# misc.net
KiCad netlist of a schematic drawn in Altium Designer
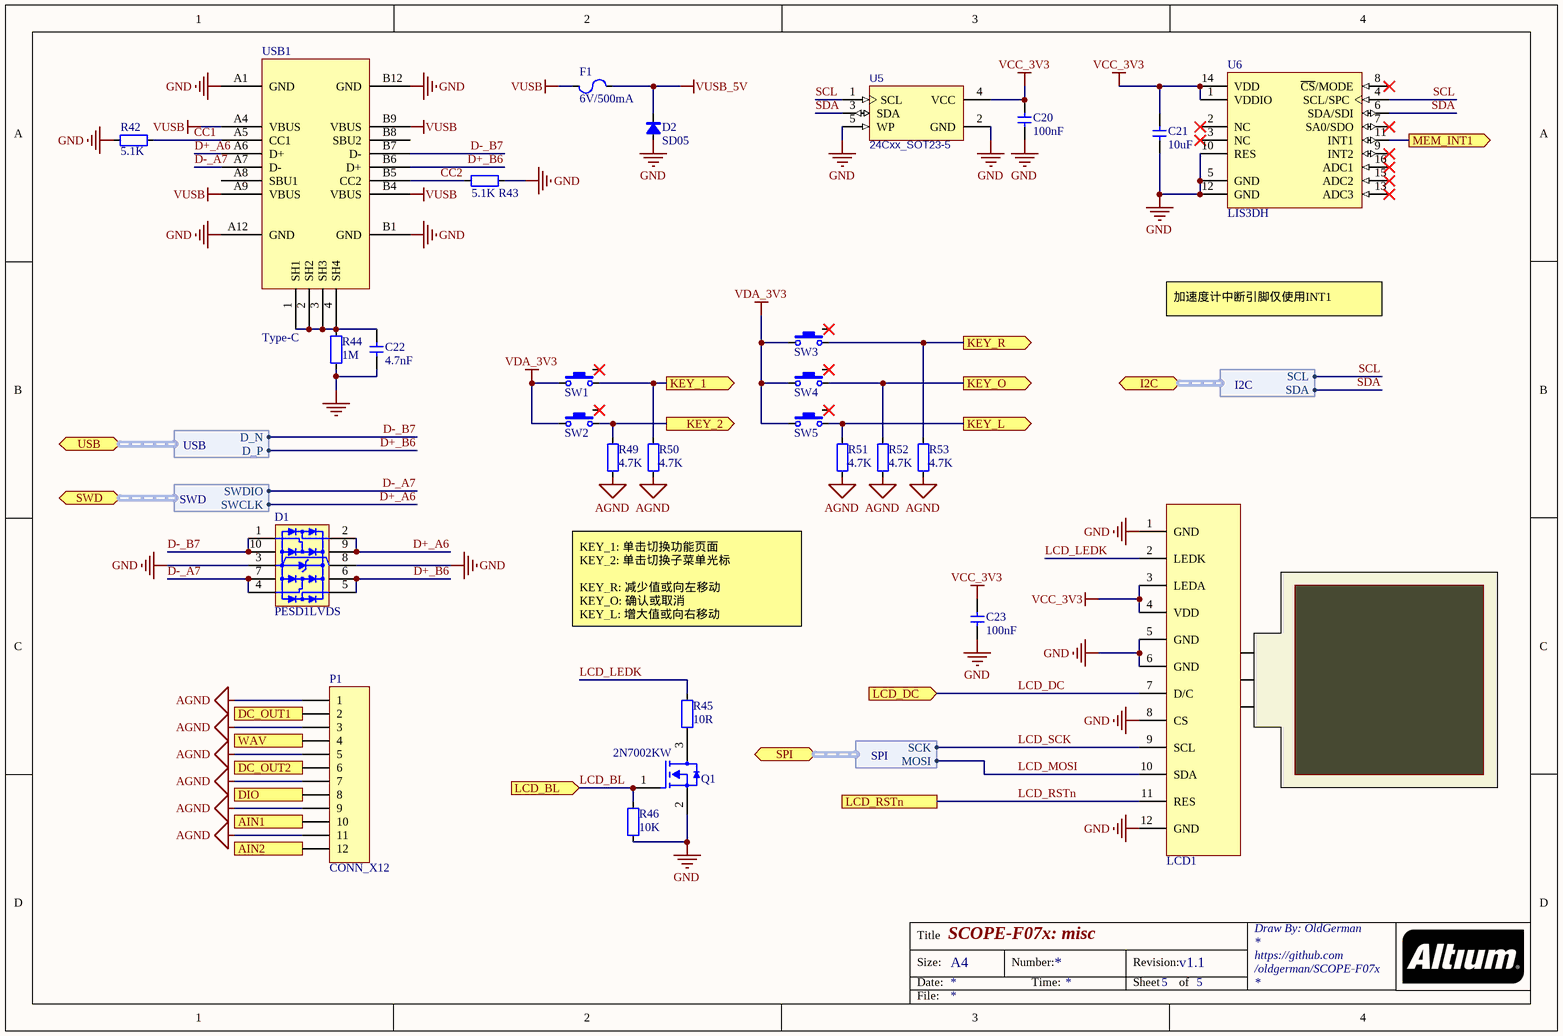
[diagram p0: misc.SchDoc]

(export (version "E")
  (design (tool "Eeschema 10.0.6"))
  (components
    (comp (ref "C20")
      (value "100nF")
      (footprint "C0402")
      (description "Capacitor")
      (libsource (lib "ODG_AD_Lib") (part "CAP"))
    )
    (comp (ref "C21")
      (value "10uF")
      (footprint "C0402")
      (description "Capacitor")
      (libsource (lib "ODG_AD_Lib") (part "CAP"))
    )
    (comp (ref "C22")
      (value "4.7nF")
      (footprint "C0402")
      (description "Capacitor")
      (libsource (lib "") (part "CAP_1"))
    )
    (comp (ref "C23")
      (value "100nF")
      (footprint "C0402")
      (description "Capacitor")
      (libsource (lib "") (part "CAP_1"))
    )
    (comp (ref "D1")
      (value "PESD1LVDS")
      (footprint "DFN2510-10_SOT1165-1")
      (description "Ultra-Low Capacitance TVS Protection")
      (fields (field (name "版权归属") "源创客"))
      (libsource (lib "ODG_AD_Lib") (part "PESD1LVDS"))
    )
    (comp (ref "D2")
      (value "SD05")
      (footprint "SOD-323")
      (description "单向 5V TVS")
      (libsource (lib "ODG_AD_Lib") (part "DIODE"))
    )
    (comp (ref "F1")
      (value "6V/500mA")
      (footprint "FUSE0603_0.5MM")
      (description "贴片自恢复保险丝")
      (libsource (lib "ODG_AD_Lib") (part "FUSE"))
    )
    (comp (ref "LCD1")
      (value "LCD_240x240")
      (footprint "LCD-240X240-1.54INCH_FLUSH_FRONT")
      (libsource (lib "ODG_AD_Lib") (part "LCD_240x240"))
    )
    (comp (ref "P1")
      (value "CONN_X12")
      (footprint "2.54MM_FEMALE_1x12_180H")
      (libsource (lib "ODG_Project") (part "CONN_X12"))
    )
    (comp (ref "Q1")
      (value "2N7002KW")
      (footprint "DIODES SOT-323-3")
      (description "N-MOS")
      (libsource (lib "ODG_AD_Lib") (part "N-MOS_123"))
    )
    (comp (ref "R42")
      (value "5.1K")
      (footprint "R0402")
      (description "Resistor")
      (libsource (lib "") (part "RES_3"))
    )
    (comp (ref "R43")
      (value "5.1K")
      (footprint "R0402")
      (description "Resistor")
      (libsource (lib "") (part "RES_1"))
    )
    (comp (ref "R44")
      (value "1M")
      (footprint "R0402")
      (description "Resistor")
      (libsource (lib "ODG_AD_Lib") (part "RES"))
    )
    (comp (ref "R45")
      (value "10R")
      (footprint "R0603")
      (description "Resistor")
      (libsource (lib "") (part "RES_2"))
    )
    (comp (ref "R46")
      (value "10K")
      (footprint "R0402")
      (description "Resistor")
      (libsource (lib "") (part "RES_2"))
    )
    (comp (ref "R49")
      (value "4.7K")
      (footprint "R0402")
      (description "Resistor")
      (libsource (lib "ODG_AD_Lib") (part "RES"))
    )
    (comp (ref "R50")
      (value "4.7K")
      (footprint "R0402")
      (description "Resistor")
      (libsource (lib "ODG_AD_Lib") (part "RES"))
    )
    (comp (ref "R51")
      (value "4.7K")
      (footprint "R0402")
      (description "Resistor")
      (libsource (lib "ODG_AD_Lib") (part "RES"))
    )
    (comp (ref "R52")
      (value "4.7K")
      (footprint "R0402")
      (description "Resistor")
      (libsource (lib "ODG_AD_Lib") (part "RES"))
    )
    (comp (ref "R53")
      (value "4.7K")
      (footprint "R0402")
      (description "Resistor")
      (libsource (lib "ODG_AD_Lib") (part "RES"))
    )
    (comp (ref "SW1")
      (value "Button-2P+PAD")
      (footprint "TACTILE_SWITCH_SMD_4.6x1.82x3.5mm_1TS003B")
      (description "Button")
      (libsource (lib "ODG_AD_Lib") (part "Button-2P+PAD"))
    )
    (comp (ref "SW2")
      (value "Button-2P+PAD")
      (footprint "TACTILE_SWITCH_SMD_4.6x1.82x3.5mm_1TS003B")
      (description "Button")
      (libsource (lib "ODG_AD_Lib") (part "Button-2P+PAD"))
    )
    (comp (ref "SW3")
      (value "Button-2P+PAD")
      (footprint "TACTILE_SWITCH_SMD_4.6x1.82x3.5mm_1TS003B")
      (description "Button")
      (libsource (lib "ODG_AD_Lib") (part "Button-2P+PAD"))
    )
    (comp (ref "SW4")
      (value "Button-2P+PAD")
      (footprint "TACTILE_SWITCH_SMD_4.6x1.82x3.5mm_1TS003B")
      (description "Button")
      (libsource (lib "ODG_AD_Lib") (part "Button-2P+PAD"))
    )
    (comp (ref "SW5")
      (value "Button-2P+PAD")
      (footprint "TACTILE_SWITCH_SMD_4.6x1.82x3.5mm_1TS003B")
      (description "Button")
      (libsource (lib "ODG_AD_Lib") (part "Button-2P+PAD"))
    )
    (comp (ref "U5")
      (value "24Cxx_SOT23-5")
      (footprint "MICROCHIP SOT-23-5 OT")
      (libsource (lib "ODG_AD_Lib") (part "24Cxx_SOT23-5"))
    )
    (comp (ref "U6") (value "LIS3DH") (footprint "LGA-16-3X3") (libsource (lib "ODG_AD_Lib") (part "LIS3DH")))
    (comp (ref "USB1")
      (value "Type-C")
      (footprint "Type-C-TOP")
      (libsource (lib "ODG_AD_Lib") (part "USB-Type-C_16P"))
    )
  )
  (nets
    (net (code "5") (name "/AIN1") (class "Default")
      (node (ref "P1") (pin "10") (pinfunction "10_10") (pintype "passive"))
    )
    (net (code "6") (name "/AIN2") (class "Default")
      (node (ref "P1") (pin "12") (pinfunction "12_12") (pintype "passive"))
    )
    (net (code "7") (name "/CC1") (class "Default")
      (node (ref "R42") (pin "1") (pinfunction "1_1") (pintype "passive"))
      (node (ref "USB1") (pin "A5") (pinfunction "CC1_A5") (pintype "passive"))
    )
    (net (code "8") (name "/CC2") (class "Default")
      (node (ref "R43") (pin "2") (pinfunction "2_2") (pintype "passive"))
      (node (ref "USB1") (pin "B5") (pinfunction "CC2_B5") (pintype "passive"))
    )
    (net (code "9") (name "/D+_A6") (class "Default")
      (node (ref "D1") (pin "2") (pinfunction "I/O_2") (pintype "passive"))
      (node (ref "D1") (pin "9") (pinfunction "GND_9") (pintype "passive"))
      (node (ref "USB1") (pin "A6") (pinfunction "D+_A6") (pintype "passive"))
    )
    (net (code "10") (name "/D+_B6") (class "Default")
      (node (ref "D1") (pin "5") (pinfunction "I/O_5") (pintype "passive"))
      (node (ref "D1") (pin "6") (pinfunction "GND_6") (pintype "passive"))
      (node (ref "USB1") (pin "B6") (pinfunction "D+_B6") (pintype "passive"))
    )
    (net (code "11") (name "/D-_A7") (class "Default")
      (node (ref "D1") (pin "4") (pinfunction "I/O_4") (pintype "passive"))
      (node (ref "D1") (pin "7") (pinfunction "GND_7") (pintype "passive"))
      (node (ref "USB1") (pin "A7") (pinfunction "D-_A7") (pintype "passive"))
    )
    (net (code "12") (name "/D-_B7") (class "Default")
      (node (ref "D1") (pin "1") (pinfunction "I/O_1") (pintype "passive"))
      (node (ref "D1") (pin "10") (pinfunction "GND_10") (pintype "passive"))
      (node (ref "USB1") (pin "B7") (pinfunction "D-_B7") (pintype "passive"))
    )
    (net (code "13") (name "/DC_OUT1") (class "Default")
      (node (ref "P1") (pin "2") (pinfunction "2_2") (pintype "passive"))
    )
    (net (code "14") (name "/DC_OUT2") (class "Default")
      (node (ref "P1") (pin "6") (pinfunction "6_6") (pintype "passive"))
    )
    (net (code "15") (name "/DIO") (class "Default")
      (node (ref "P1") (pin "8") (pinfunction "8_8") (pintype "passive"))
    )
    (net (code "16") (name "/KEY_1") (class "Default")
      (node (ref "R50") (pin "1") (pinfunction "1_1") (pintype "passive"))
      (node (ref "SW1") (pin "2") (pinfunction "2_2") (pintype "passive"))
    )
    (net (code "17") (name "/KEY_2") (class "Default")
      (node (ref "R49") (pin "1") (pinfunction "1_1") (pintype "passive"))
      (node (ref "SW2") (pin "2") (pinfunction "2_2") (pintype "passive"))
    )
    (net (code "18") (name "/KEY_L") (class "Default")
      (node (ref "R51") (pin "1") (pinfunction "1_1") (pintype "passive"))
      (node (ref "SW5") (pin "2") (pinfunction "2_2") (pintype "passive"))
    )
    (net (code "19") (name "/KEY_O") (class "Default")
      (node (ref "R52") (pin "1") (pinfunction "1_1") (pintype "passive"))
      (node (ref "SW4") (pin "2") (pinfunction "2_2") (pintype "passive"))
    )
    (net (code "20") (name "/KEY_R") (class "Default")
      (node (ref "R53") (pin "1") (pinfunction "1_1") (pintype "passive"))
      (node (ref "SW3") (pin "2") (pinfunction "2_2") (pintype "passive"))
    )
    (net (code "21") (name "/LCD_BL") (class "Default")
      (node (ref "Q1") (pin "1") (pinfunction "G_1") (pintype "passive"))
      (node (ref "R46") (pin "2") (pinfunction "2_2") (pintype "passive"))
    )
    (net (code "22") (name "/LCD_DC") (class "Default")
      (node (ref "LCD1") (pin "7") (pinfunction "D/C_7") (pintype "passive"))
    )
    (net (code "23") (name "/LCD_LEDK") (class "Default")
      (node (ref "LCD1") (pin "2") (pinfunction "LEDK_2") (pintype "passive"))
      (node (ref "R45") (pin "2") (pinfunction "2_2") (pintype "passive"))
    )
    (net (code "24") (name "/LCD_MOSI") (class "Default")
      (node (ref "LCD1") (pin "10") (pinfunction "SDA_10") (pintype "passive"))
    )
    (net (code "25") (name "/LCD_RSTn") (class "Default")
      (node (ref "LCD1") (pin "11") (pinfunction "RES_11") (pintype "passive"))
    )
    (net (code "26") (name "/LCD_SCK") (class "Default")
      (node (ref "LCD1") (pin "9") (pinfunction "SCL_9") (pintype "passive"))
    )
    (net (code "27") (name "/MEM_INT1") (class "Default")
      (node (ref "U6") (pin "11") (pinfunction "INT1_11") (pintype "bidirectional"))
    )
    (net (code "28") (name "/SCL") (class "Default")
      (node (ref "U5") (pin "1") (pinfunction "SCL_1") (pintype "input"))
      (node (ref "U6") (pin "4") (pinfunction "SCL/SPC_4") (pintype "input"))
    )
    (net (code "29") (name "/SDA") (class "Default")
      (node (ref "U5") (pin "3") (pinfunction "SDA_3") (pintype "bidirectional"))
      (node (ref "U6") (pin "6") (pinfunction "SDA/SDI_6") (pintype "bidirectional"))
    )
    (net (code "30") (name "/WAV") (class "Default")
      (node (ref "P1") (pin "4") (pinfunction "4_4") (pintype "passive"))
    )
    (net (code "35") (name "AGND") (class "Default")
      (node (ref "P1") (pin "1") (pinfunction "1_1") (pintype "passive"))
      (node (ref "P1") (pin "11") (pinfunction "11_11") (pintype "passive"))
      (node (ref "P1") (pin "3") (pinfunction "3_3") (pintype "passive"))
      (node (ref "P1") (pin "5") (pinfunction "5_5") (pintype "passive"))
      (node (ref "P1") (pin "7") (pinfunction "7_7") (pintype "passive"))
      (node (ref "P1") (pin "9") (pinfunction "9_9") (pintype "passive"))
      (node (ref "R49") (pin "2") (pinfunction "2_2") (pintype "passive"))
      (node (ref "R50") (pin "2") (pinfunction "2_2") (pintype "passive"))
      (node (ref "R51") (pin "2") (pinfunction "2_2") (pintype "passive"))
      (node (ref "R52") (pin "2") (pinfunction "2_2") (pintype "passive"))
      (node (ref "R53") (pin "2") (pinfunction "2_2") (pintype "passive"))
    )
    (net (code "36") (name "GND") (class "Default")
      (node (ref "C20") (pin "2") (pinfunction "2_2") (pintype "passive"))
      (node (ref "C21") (pin "2") (pinfunction "2_2") (pintype "passive"))
      (node (ref "C22") (pin "2") (pinfunction "2_2") (pintype "passive"))
      (node (ref "C23") (pin "1") (pinfunction "1_1") (pintype "passive"))
      (node (ref "D1") (pin "3") (pinfunction "GND_3") (pintype "passive"))
      (node (ref "D1") (pin "8") (pinfunction "GND_8") (pintype "passive"))
      (node (ref "D2") (pin "1") (pinfunction "A_1") (pintype "passive"))
      (node (ref "LCD1") (pin "1") (pinfunction "GND_1") (pintype "passive"))
      (node (ref "LCD1") (pin "12") (pinfunction "GND_12") (pintype "passive"))
      (node (ref "LCD1") (pin "5") (pinfunction "GND_5") (pintype "passive"))
      (node (ref "LCD1") (pin "6") (pinfunction "GND_6") (pintype "passive"))
      (node (ref "LCD1") (pin "8") (pinfunction "CS_8") (pintype "passive"))
      (node (ref "Q1") (pin "2") (pinfunction "S_2") (pintype "passive"))
      (node (ref "R42") (pin "2") (pinfunction "2_2") (pintype "passive"))
      (node (ref "R43") (pin "1") (pinfunction "1_1") (pintype "passive"))
      (node (ref "R44") (pin "2") (pinfunction "2_2") (pintype "passive"))
      (node (ref "R46") (pin "1") (pinfunction "1_1") (pintype "passive"))
      (node (ref "U5") (pin "2") (pinfunction "GND_2") (pintype "passive"))
      (node (ref "U5") (pin "5") (pinfunction "WP_5") (pintype "input"))
      (node (ref "U6") (pin "10") (pinfunction "RES_10") (pintype "power_in"))
      (node (ref "U6") (pin "12") (pinfunction "GND_12") (pintype "power_in"))
      (node (ref "U6") (pin "5") (pinfunction "GND_5") (pintype "power_in"))
      (node (ref "USB1") (pin "A1") (pinfunction "GND_A1") (pintype "passive"))
      (node (ref "USB1") (pin "A12") (pinfunction "GND_A12") (pintype "passive"))
      (node (ref "USB1") (pin "B1") (pinfunction "GND_B1") (pintype "passive"))
      (node (ref "USB1") (pin "B12") (pinfunction "GND_B12") (pintype "passive"))
    )
    (net (code "37") (name "Net-(Q1-D)") (class "Default")
      (node (ref "Q1") (pin "3") (pinfunction "D_3") (pintype "passive"))
      (node (ref "R45") (pin "1") (pinfunction "1_1") (pintype "passive"))
    )
    (net (code "38") (name "Net-(USB1-SH1)") (class "Default")
      (node (ref "C22") (pin "1") (pinfunction "1_1") (pintype "passive"))
      (node (ref "R44") (pin "1") (pinfunction "1_1") (pintype "passive"))
      (node (ref "USB1") (pin "1") (pinfunction "SH1_1") (pintype "passive"))
      (node (ref "USB1") (pin "2") (pinfunction "SH2_2") (pintype "passive"))
      (node (ref "USB1") (pin "3") (pinfunction "SH3_3") (pintype "passive"))
      (node (ref "USB1") (pin "4") (pinfunction "SH4_4") (pintype "passive"))
    )
    (net (code "39") (name "VCC_3V3") (class "Default")
      (node (ref "C20") (pin "1") (pinfunction "1_1") (pintype "passive"))
      (node (ref "C21") (pin "1") (pinfunction "1_1") (pintype "passive"))
      (node (ref "C23") (pin "2") (pinfunction "2_2") (pintype "passive"))
      (node (ref "LCD1") (pin "3") (pinfunction "LEDA_3") (pintype "passive"))
      (node (ref "LCD1") (pin "4") (pinfunction "VDD_4") (pintype "passive"))
      (node (ref "U5") (pin "4") (pinfunction "VCC_4") (pintype "passive"))
      (node (ref "U6") (pin "1") (pinfunction "VDDIO_1") (pintype "power_in"))
      (node (ref "U6") (pin "14") (pinfunction "VDD_14") (pintype "power_in"))
    )
    (net (code "40") (name "VDA_3V3") (class "Default")
      (node (ref "SW1") (pin "1") (pinfunction "1_1") (pintype "passive"))
      (node (ref "SW2") (pin "1") (pinfunction "1_1") (pintype "passive"))
      (node (ref "SW3") (pin "1") (pinfunction "1_1") (pintype "passive"))
      (node (ref "SW4") (pin "1") (pinfunction "1_1") (pintype "passive"))
      (node (ref "SW5") (pin "1") (pinfunction "1_1") (pintype "passive"))
    )
    (net (code "41") (name "VUSB") (class "Default")
      (node (ref "F1") (pin "1") (pinfunction "1_1") (pintype "passive"))
      (node (ref "USB1") (pin "A4") (pinfunction "VBUS_A4") (pintype "passive"))
      (node (ref "USB1") (pin "A9") (pinfunction "VBUS_A9") (pintype "passive"))
      (node (ref "USB1") (pin "B4") (pinfunction "VBUS_B4") (pintype "passive"))
      (node (ref "USB1") (pin "B9") (pinfunction "VBUS_B9") (pintype "passive"))
    )
    (net (code "42") (name "VUSB_5V") (class "Default")
      (node (ref "D2") (pin "2") (pinfunction "C_2") (pintype "passive"))
      (node (ref "F1") (pin "2") (pinfunction "2_2") (pintype "passive"))
    )
    (net (code "43") (name "unconnected-(SW1-Pad3)") (class "Default")
      (node (ref "SW1") (pin "3") (pinfunction "3_3") (pintype "passive+no_connect"))
    )
    (net (code "44") (name "unconnected-(SW2-Pad3)") (class "Default")
      (node (ref "SW2") (pin "3") (pinfunction "3_3") (pintype "passive+no_connect"))
    )
    (net (code "45") (name "unconnected-(SW3-Pad3)") (class "Default")
      (node (ref "SW3") (pin "3") (pinfunction "3_3") (pintype "passive+no_connect"))
    )
    (net (code "46") (name "unconnected-(SW4-Pad3)") (class "Default")
      (node (ref "SW4") (pin "3") (pinfunction "3_3") (pintype "passive+no_connect"))
    )
    (net (code "47") (name "unconnected-(SW5-Pad3)") (class "Default")
      (node (ref "SW5") (pin "3") (pinfunction "3_3") (pintype "passive+no_connect"))
    )
    (net (code "48") (name "unconnected-(U6-ADC1-Pad16)") (class "Default")
      (node (ref "U6") (pin "16") (pinfunction "ADC1_16") (pintype "input+no_connect"))
    )
    (net (code "49") (name "unconnected-(U6-ADC2-Pad15)") (class "Default")
      (node (ref "U6") (pin "15") (pinfunction "ADC2_15") (pintype "input+no_connect"))
    )
    (net (code "50") (name "unconnected-(U6-ADC3-Pad13)") (class "Default")
      (node (ref "U6") (pin "13") (pinfunction "ADC3_13") (pintype "input+no_connect"))
    )
    (net (code "51") (name "unconnected-(U6-INT2-Pad9)") (class "Default")
      (node (ref "U6") (pin "9") (pinfunction "INT2_9") (pintype "bidirectional+no_connect"))
    )
    (net (code "52") (name "unconnected-(U6-NC-Pad2)") (class "Default")
      (node (ref "U6") (pin "2") (pinfunction "NC_2") (pintype "power_in+no_connect"))
    )
    (net (code "53") (name "unconnected-(U6-NC-Pad3)") (class "Default")
      (node (ref "U6") (pin "3") (pinfunction "NC_3") (pintype "power_in+no_connect"))
    )
    (net (code "54") (name "unconnected-(U6-SA0{slash}SDO-Pad7)") (class "Default")
      (node (ref "U6") (pin "7") (pinfunction "SA0/SDO_7") (pintype "bidirectional+no_connect"))
    )
    (net (code "55") (name "unconnected-(U6-~{CS}{slash}MODE-Pad8)") (class "Default")
      (node (ref "U6") (pin "8") (pinfunction "~{CS}/MODE_8") (pintype "input+no_connect"))
    )
    (net (code "56") (name "unconnected-(USB1-SBU1-PadA8)") (class "Default")
      (node (ref "USB1") (pin "A8") (pinfunction "SBU1_A8") (pintype "passive"))
    )
    (net (code "57") (name "unconnected-(USB1-SBU2-PadB8)") (class "Default")
      (node (ref "USB1") (pin "B8") (pinfunction "SBU2_B8") (pintype "passive"))
    )
  )
)
